# MB_downlink_phy.net
KiCad netlist of a schematic drawn in Altium Designer
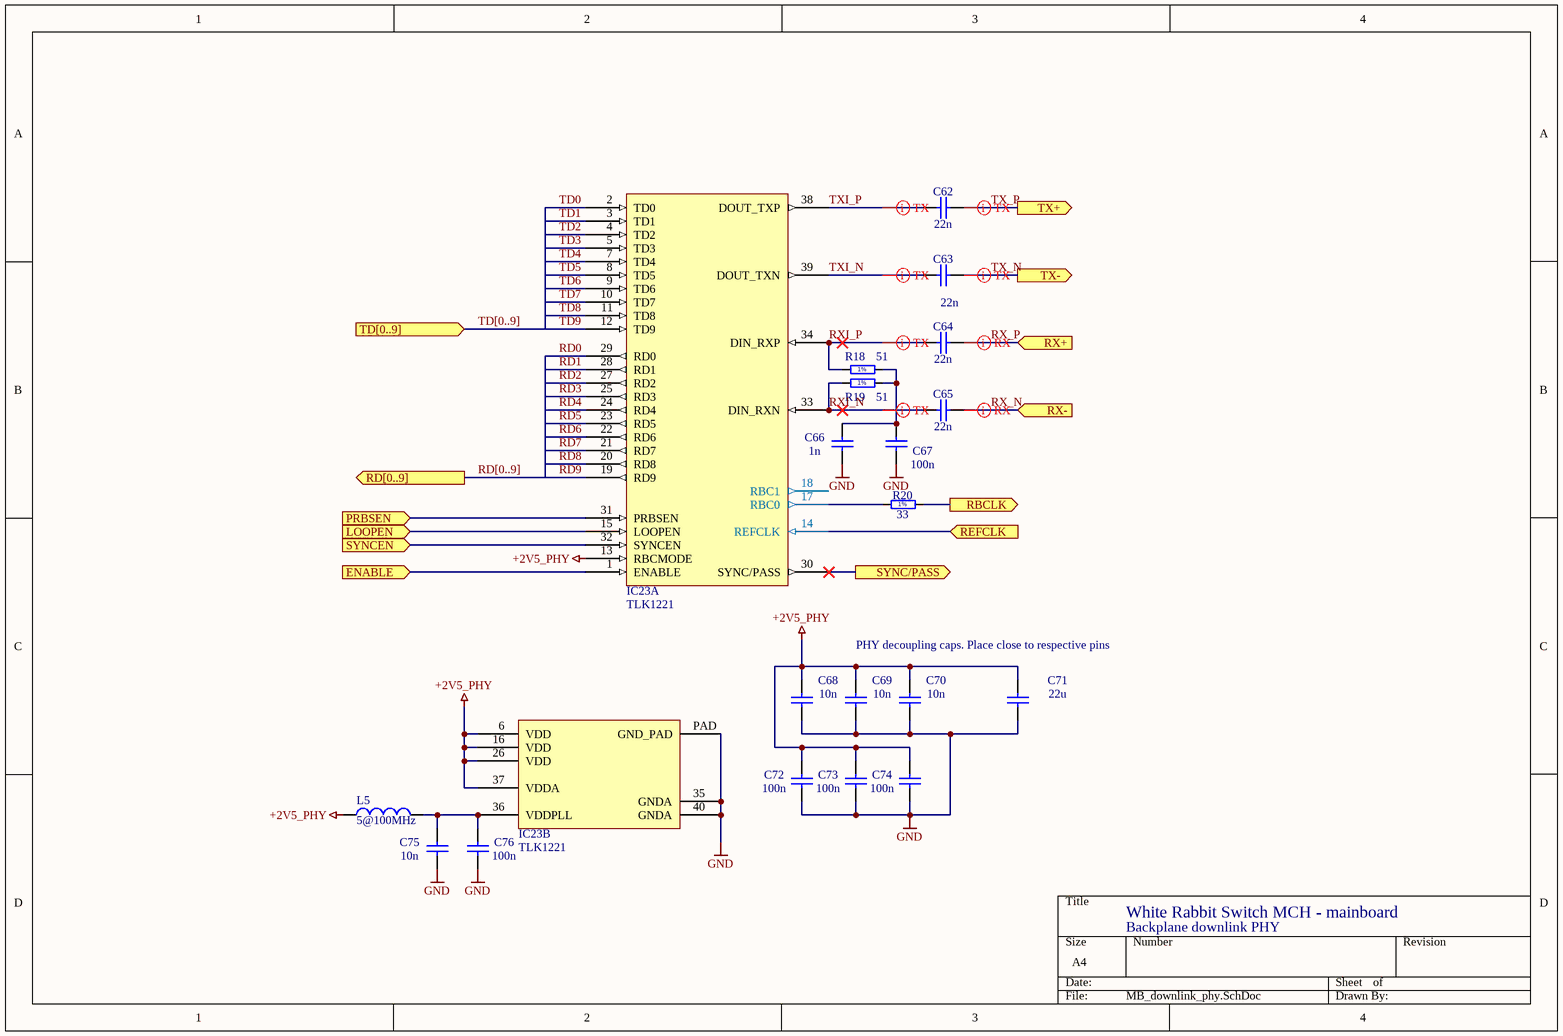
[diagram p0: MB_downlink_phy.SchDoc]

(export (version "E")
  (design (tool "Eeschema 10.0.6"))
  (components
    (comp (ref "C62")
      (value "22n")
      (footprint "CAPC1005X55N")
      (description "Non-polarised capacitor")
      (fields
        (field (name "PART NUMBER") "CC0402_22NF_16V_10%_X7R")
        (field (name "VOLTAGE") "16V")
        (field (name "AUTHOR") "CERN DEM JLC")
      )
      (libsource (lib "Capacitors") (part "Capacitor - non polarized"))
    )
    (comp (ref "C63")
      (value "22n")
      (footprint "CAPC1005X55N")
      (description "Non-polarised capacitor")
      (fields
        (field (name "PART NUMBER") "CC0402_22NF_16V_10%_X7R")
        (field (name "VOLTAGE") "16V")
        (field (name "AUTHOR") "CERN DEM JLC")
      )
      (libsource (lib "Capacitors") (part "Capacitor - non polarized"))
    )
    (comp (ref "C64")
      (value "22n")
      (footprint "CAPC1005X55N")
      (description "Non-polarised capacitor")
      (fields
        (field (name "PART NUMBER") "CC0402_22NF_16V_10%_X7R")
        (field (name "VOLTAGE") "16V")
        (field (name "AUTHOR") "CERN DEM JLC")
      )
      (libsource (lib "Capacitors") (part "Capacitor - non polarized"))
    )
    (comp (ref "C65")
      (value "22n")
      (footprint "CAPC1005X55N")
      (description "Non-polarised capacitor")
      (fields
        (field (name "PART NUMBER") "CC0402_22NF_16V_10%_X7R")
        (field (name "VOLTAGE") "16V")
        (field (name "AUTHOR") "CERN DEM JLC")
      )
      (libsource (lib "Capacitors") (part "Capacitor - non polarized"))
    )
    (comp (ref "C66")
      (value "1n")
      (footprint "CAPC1005X55N")
      (description "Non-polarised capacitor")
      (fields
        (field (name "PART NUMBER") "CC0402_1.0NF_50V_10%_X7R")
        (field (name "VOLTAGE") "50V")
        (field (name "AUTHOR") "CERN DEM JLC")
      )
      (libsource (lib "Capacitors") (part "Capacitor - non polarized"))
    )
    (comp (ref "C67")
      (value "100n")
      (footprint "CAPC1005X55N")
      (description "Non-polarised capacitor")
      (fields
        (field (name "PART NUMBER") "CC0402_100NF_16V_10%_X7R")
        (field (name "VOLTAGE") "16V")
        (field (name "AUTHOR") "CERN DEM JLC")
      )
      (libsource (lib "Capacitors") (part "Capacitor - non polarized"))
    )
    (comp (ref "C68")
      (value "10n")
      (footprint "CAPC1005X55N")
      (description "Non-polarised capacitor")
      (fields
        (field (name "PART NUMBER") "CC0402_10NF_16V_10%_X7R")
        (field (name "VOLTAGE") "16V")
        (field (name "AUTHOR") "CERN DEM JLC")
      )
      (libsource (lib "Capacitors") (part "Capacitor - non polarized"))
    )
    (comp (ref "C69")
      (value "10n")
      (footprint "CAPC1005X55N")
      (description "Non-polarised capacitor")
      (fields
        (field (name "PART NUMBER") "CC0402_10NF_16V_10%_X7R")
        (field (name "VOLTAGE") "16V")
        (field (name "AUTHOR") "CERN DEM JLC")
      )
      (libsource (lib "Capacitors") (part "Capacitor - non polarized"))
    )
    (comp (ref "C70")
      (value "10n")
      (footprint "CAPC1005X55N")
      (description "Non-polarised capacitor")
      (fields
        (field (name "PART NUMBER") "CC0402_10NF_16V_10%_X7R")
        (field (name "VOLTAGE") "16V")
        (field (name "AUTHOR") "CERN DEM JLC")
      )
      (libsource (lib "Capacitors") (part "Capacitor - non polarized"))
    )
    (comp (ref "C71")
      (value "22u")
      (footprint "CAPC2012X135N")
      (description "Non-polarised capacitor")
      (fields
        (field (name "PART NUMBER") "CC0805_22uF_6.3V_20%_X5R")
        (field (name "VOLTAGE") "6.3V")
        (field (name "AUTHOR") "CERN DEM JLC")
      )
      (libsource (lib "Capacitors") (part "Capacitor - non polarized"))
    )
    (comp (ref "C72")
      (value "100n")
      (footprint "CAPC1005X55N")
      (description "Non-polarised capacitor")
      (fields
        (field (name "PART NUMBER") "CC0402_100NF_16V_10%_X7R")
        (field (name "VOLTAGE") "16V")
        (field (name "AUTHOR") "CERN DEM JLC")
      )
      (libsource (lib "Capacitors") (part "Capacitor - non polarized"))
    )
    (comp (ref "C73")
      (value "100n")
      (footprint "CAPC1005X55N")
      (description "Non-polarised capacitor")
      (fields
        (field (name "PART NUMBER") "CC0402_100NF_16V_10%_X7R")
        (field (name "VOLTAGE") "16V")
        (field (name "AUTHOR") "CERN DEM JLC")
      )
      (libsource (lib "Capacitors") (part "Capacitor - non polarized"))
    )
    (comp (ref "C74")
      (value "100n")
      (footprint "CAPC1005X55N")
      (description "Non-polarised capacitor")
      (fields
        (field (name "PART NUMBER") "CC0402_100NF_16V_10%_X7R")
        (field (name "VOLTAGE") "16V")
        (field (name "AUTHOR") "CERN DEM JLC")
      )
      (libsource (lib "Capacitors") (part "Capacitor - non polarized"))
    )
    (comp (ref "C75")
      (value "10n")
      (footprint "CAPC1005X55N")
      (description "Non-polarised capacitor")
      (fields
        (field (name "PART NUMBER") "CC0402_10NF_16V_10%_X7R")
        (field (name "VOLTAGE") "16V")
        (field (name "AUTHOR") "CERN DEM JLC")
      )
      (libsource (lib "Capacitors") (part "Capacitor - non polarized"))
    )
    (comp (ref "C76")
      (value "100n")
      (footprint "CAPC1005X55N")
      (description "Non-polarised capacitor")
      (fields
        (field (name "PART NUMBER") "CC0402_100NF_16V_10%_X7R")
        (field (name "VOLTAGE") "16V")
        (field (name "AUTHOR") "CERN DEM JLC")
      )
      (libsource (lib "Capacitors") (part "Capacitor - non polarized"))
    )
    (comp (ref "IC23")
      (value "TLK1221")
      (footprint "QFN40_powerpad")
      (description "Texas Instruments Gigabit Ethernet PHY with deterministic clocking and LVPECL output interface")
      (libsource (lib "wr_switch") (part "TLK1221"))
    )
    (comp (ref "L5")
      (value "5@100MHz")
      (footprint "INDC1608-0603")
      (description "Ferrite bead")
      (fields (field (name "Comment") "Inductor") (field (name "PUBLISHER") "Altium Limited"))
      (libsource (lib "Miscellaneous Devices") (part "Inductor"))
    )
    (comp (ref "R18")
      (value "51")
      (footprint "RESC1005X40N")
      (description "Resistor - 1%")
      (fields
        (field (name "PART NUMBER") "R0402_51R_1%_0.0625W_100PPM")
        (field (name "POWER") "0.0625W")
        (field (name "AUTHOR") "CERN DEM JLC")
      )
      (libsource (lib "Resistors") (part "Resistor - 1%"))
    )
    (comp (ref "R19")
      (value "51")
      (footprint "RESC1005X40N")
      (description "Resistor - 1%")
      (fields
        (field (name "PART NUMBER") "R0402_51R_1%_0.0625W_100PPM")
        (field (name "POWER") "0.0625W")
        (field (name "AUTHOR") "CERN DEM JLC")
      )
      (libsource (lib "Resistors") (part "Resistor - 1%"))
    )
    (comp (ref "R20")
      (value "33")
      (footprint "RESC1005X40N")
      (description "Resistor - 1%")
      (fields
        (field (name "PART NUMBER") "R0402_33R_1%_0.0625W_100PPM")
        (field (name "POWER") "0.0625W")
        (field (name "AUTHOR") "CERN DEM JLC")
      )
      (libsource (lib "Resistors") (part "Resistor - 1%"))
    )
  )
  (nets
    (net (code "1") (name "+2V5_PHY") (class "Default")
      (node (ref "C68") (pin "2") (pinfunction "2_2") (pintype "passive"))
      (node (ref "C69") (pin "2") (pinfunction "2_2") (pintype "passive"))
      (node (ref "C70") (pin "2") (pinfunction "2_2") (pintype "passive"))
      (node (ref "C71") (pin "2") (pinfunction "2_2") (pintype "passive"))
      (node (ref "C72") (pin "2") (pinfunction "2_2") (pintype "passive"))
      (node (ref "C73") (pin "2") (pinfunction "2_2") (pintype "passive"))
      (node (ref "C74") (pin "2") (pinfunction "2_2") (pintype "passive"))
      (node (ref "IC23") (pin "13") (pinfunction "RBCMODE_13") (pintype "input"))
      (node (ref "IC23") (pin "16") (pinfunction "VDD_16") (pintype "power_in"))
      (node (ref "IC23") (pin "26") (pinfunction "VDD_26") (pintype "power_in"))
      (node (ref "IC23") (pin "37") (pinfunction "VDDA_37") (pintype "power_in"))
      (node (ref "IC23") (pin "6") (pinfunction "VDD_6") (pintype "power_in"))
      (node (ref "L5") (pin "1") (pinfunction "1_1") (pintype "passive"))
    )
    (net (code "2") (name "/ENABLE") (class "Default")
      (node (ref "IC23") (pin "1") (pinfunction "ENABLE_1") (pintype "input"))
    )
    (net (code "3") (name "/LOOPEN") (class "Default")
      (node (ref "IC23") (pin "15") (pinfunction "LOOPEN_15") (pintype "input"))
    )
    (net (code "4") (name "/PRBSEN") (class "Default")
      (node (ref "IC23") (pin "31") (pinfunction "PRBSEN_31") (pintype "input"))
    )
    (net (code "5") (name "/RBCLK") (class "Default")
      (node (ref "R20") (pin "2") (pinfunction "2_2") (pintype "passive"))
    )
    (net (code "6") (name "/RD0") (class "Default")
      (node (ref "IC23") (pin "29") (pinfunction "RD0_29") (pintype "output"))
    )
    (net (code "7") (name "/RD1") (class "Default")
      (node (ref "IC23") (pin "28") (pinfunction "RD1_28") (pintype "output"))
    )
    (net (code "8") (name "/RD2") (class "Default")
      (node (ref "IC23") (pin "27") (pinfunction "RD2_27") (pintype "output"))
    )
    (net (code "9") (name "/RD3") (class "Default")
      (node (ref "IC23") (pin "25") (pinfunction "RD3_25") (pintype "output"))
    )
    (net (code "10") (name "/RD4") (class "Default")
      (node (ref "IC23") (pin "24") (pinfunction "RD4_24") (pintype "output"))
    )
    (net (code "11") (name "/RD5") (class "Default")
      (node (ref "IC23") (pin "23") (pinfunction "RD5_23") (pintype "output"))
    )
    (net (code "12") (name "/RD6") (class "Default")
      (node (ref "IC23") (pin "22") (pinfunction "RD6_22") (pintype "output"))
    )
    (net (code "13") (name "/RD7") (class "Default")
      (node (ref "IC23") (pin "21") (pinfunction "RD7_21") (pintype "output"))
    )
    (net (code "14") (name "/RD8") (class "Default")
      (node (ref "IC23") (pin "20") (pinfunction "RD8_20") (pintype "output"))
    )
    (net (code "15") (name "/RD9") (class "Default")
      (node (ref "IC23") (pin "19") (pinfunction "RD9_19") (pintype "output"))
    )
    (net (code "17") (name "/REFCLK") (class "Default")
      (node (ref "IC23") (pin "14") (pinfunction "REFCLK_14") (pintype "input"))
    )
    (net (code "18") (name "/RXI_N") (class "Default")
      (node (ref "C65") (pin "1") (pinfunction "1_1") (pintype "passive"))
      (node (ref "IC23") (pin "33") (pinfunction "DIN_RXN_33") (pintype "input"))
      (node (ref "R19") (pin "1") (pinfunction "1_1") (pintype "passive"))
    )
    (net (code "19") (name "/RXI_P") (class "Default")
      (node (ref "C64") (pin "1") (pinfunction "1_1") (pintype "passive"))
      (node (ref "IC23") (pin "34") (pinfunction "DIN_RXP_34") (pintype "input"))
      (node (ref "R18") (pin "1") (pinfunction "1_1") (pintype "passive"))
    )
    (net (code "20") (name "/RX_N") (class "Default")
      (node (ref "C65") (pin "2") (pinfunction "2_2") (pintype "passive"))
    )
    (net (code "21") (name "/RX_P") (class "Default")
      (node (ref "C64") (pin "2") (pinfunction "2_2") (pintype "passive"))
    )
    (net (code "22") (name "/SYNCEN") (class "Default")
      (node (ref "IC23") (pin "32") (pinfunction "SYNCEN_32") (pintype "input"))
    )
    (net (code "23") (name "/SYNC{slash}PASS") (class "Default")
      (node (ref "IC23") (pin "30") (pinfunction "SYNC/PASS_30") (pintype "output+no_connect"))
    )
    (net (code "24") (name "/TD0") (class "Default")
      (node (ref "IC23") (pin "2") (pinfunction "TD0_2") (pintype "input"))
    )
    (net (code "25") (name "/TD1") (class "Default")
      (node (ref "IC23") (pin "3") (pinfunction "TD1_3") (pintype "input"))
    )
    (net (code "26") (name "/TD2") (class "Default")
      (node (ref "IC23") (pin "4") (pinfunction "TD2_4") (pintype "input"))
    )
    (net (code "27") (name "/TD3") (class "Default")
      (node (ref "IC23") (pin "5") (pinfunction "TD3_5") (pintype "input"))
    )
    (net (code "28") (name "/TD4") (class "Default")
      (node (ref "IC23") (pin "7") (pinfunction "TD4_7") (pintype "input"))
    )
    (net (code "29") (name "/TD5") (class "Default")
      (node (ref "IC23") (pin "8") (pinfunction "TD5_8") (pintype "input"))
    )
    (net (code "30") (name "/TD6") (class "Default")
      (node (ref "IC23") (pin "9") (pinfunction "TD6_9") (pintype "input"))
    )
    (net (code "31") (name "/TD7") (class "Default")
      (node (ref "IC23") (pin "10") (pinfunction "TD7_10") (pintype "input"))
    )
    (net (code "32") (name "/TD8") (class "Default")
      (node (ref "IC23") (pin "11") (pinfunction "TD8_11") (pintype "input"))
    )
    (net (code "33") (name "/TD9") (class "Default")
      (node (ref "IC23") (pin "12") (pinfunction "TD9_12") (pintype "input"))
    )
    (net (code "35") (name "/TXI_N") (class "Default")
      (node (ref "C63") (pin "1") (pinfunction "1_1") (pintype "passive"))
      (node (ref "IC23") (pin "39") (pinfunction "DOUT_TXN_39") (pintype "output"))
    )
    (net (code "36") (name "/TXI_P") (class "Default")
      (node (ref "C62") (pin "1") (pinfunction "1_1") (pintype "passive"))
      (node (ref "IC23") (pin "38") (pinfunction "DOUT_TXP_38") (pintype "output"))
    )
    (net (code "37") (name "/TX_N") (class "Default")
      (node (ref "C63") (pin "2") (pinfunction "2_2") (pintype "passive"))
    )
    (net (code "38") (name "/TX_P") (class "Default")
      (node (ref "C62") (pin "2") (pinfunction "2_2") (pintype "passive"))
    )
    (net (code "39") (name "GND") (class "Default")
      (node (ref "C66") (pin "1") (pinfunction "1_1") (pintype "passive"))
      (node (ref "C67") (pin "1") (pinfunction "1_1") (pintype "passive"))
      (node (ref "C68") (pin "1") (pinfunction "1_1") (pintype "passive"))
      (node (ref "C69") (pin "1") (pinfunction "1_1") (pintype "passive"))
      (node (ref "C70") (pin "1") (pinfunction "1_1") (pintype "passive"))
      (node (ref "C71") (pin "1") (pinfunction "1_1") (pintype "passive"))
      (node (ref "C72") (pin "1") (pinfunction "1_1") (pintype "passive"))
      (node (ref "C73") (pin "1") (pinfunction "1_1") (pintype "passive"))
      (node (ref "C74") (pin "1") (pinfunction "1_1") (pintype "passive"))
      (node (ref "C75") (pin "1") (pinfunction "1_1") (pintype "passive"))
      (node (ref "C76") (pin "1") (pinfunction "1_1") (pintype "passive"))
      (node (ref "IC23") (pin "35") (pinfunction "GNDA_35") (pintype "power_in"))
      (node (ref "IC23") (pin "40") (pinfunction "GNDA_40") (pintype "power_in"))
      (node (ref "IC23") (pin "PAD") (pinfunction "GND_PAD_PAD") (pintype "power_in"))
    )
    (net (code "40") (name "Net-(C66-Pad2)") (class "Default")
      (node (ref "C66") (pin "2") (pinfunction "2_2") (pintype "passive"))
      (node (ref "C67") (pin "2") (pinfunction "2_2") (pintype "passive"))
      (node (ref "R18") (pin "2") (pinfunction "2_2") (pintype "passive"))
      (node (ref "R19") (pin "2") (pinfunction "2_2") (pintype "passive"))
    )
    (net (code "41") (name "Net-(IC23A-RBC0)") (class "Default")
      (node (ref "IC23") (pin "17") (pinfunction "RBC0_17") (pintype "output"))
      (node (ref "R20") (pin "1") (pinfunction "1_1") (pintype "passive"))
    )
    (net (code "42") (name "Net-(IC23B-VDDPLL)") (class "Default")
      (node (ref "C75") (pin "2") (pinfunction "2_2") (pintype "passive"))
      (node (ref "C76") (pin "2") (pinfunction "2_2") (pintype "passive"))
      (node (ref "IC23") (pin "36") (pinfunction "VDDPLL_36") (pintype "power_in"))
      (node (ref "L5") (pin "2") (pinfunction "2_2") (pintype "passive"))
    )
    (net (code "43") (name "unconnected-(IC23A-RBC1-Pad18)") (class "Default")
      (node (ref "IC23") (pin "18") (pinfunction "RBC1_18") (pintype "output"))
    )
  )
)
